# COEXPIX_schematics.net
KiCad netlist of a schematic drawn in Altium Designer
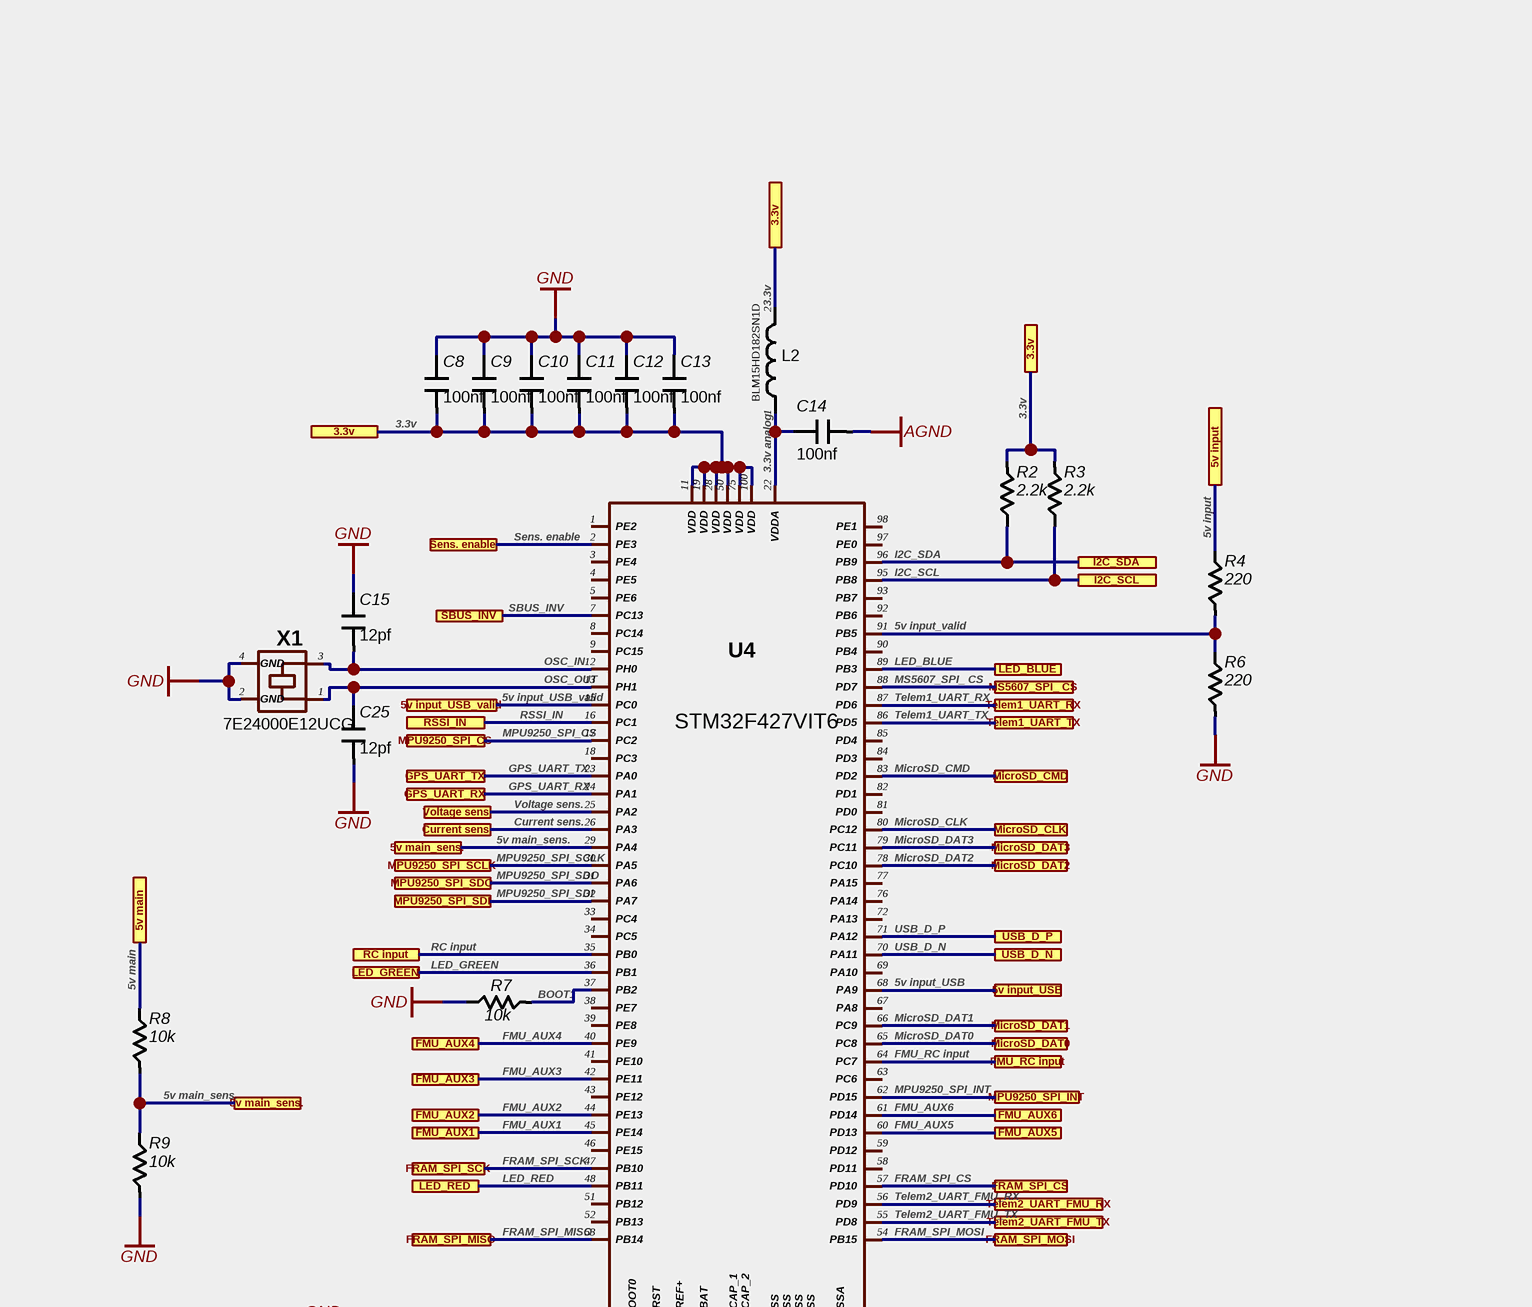
[diagram p0: COEXPIX schematics.SchDoc, top left]
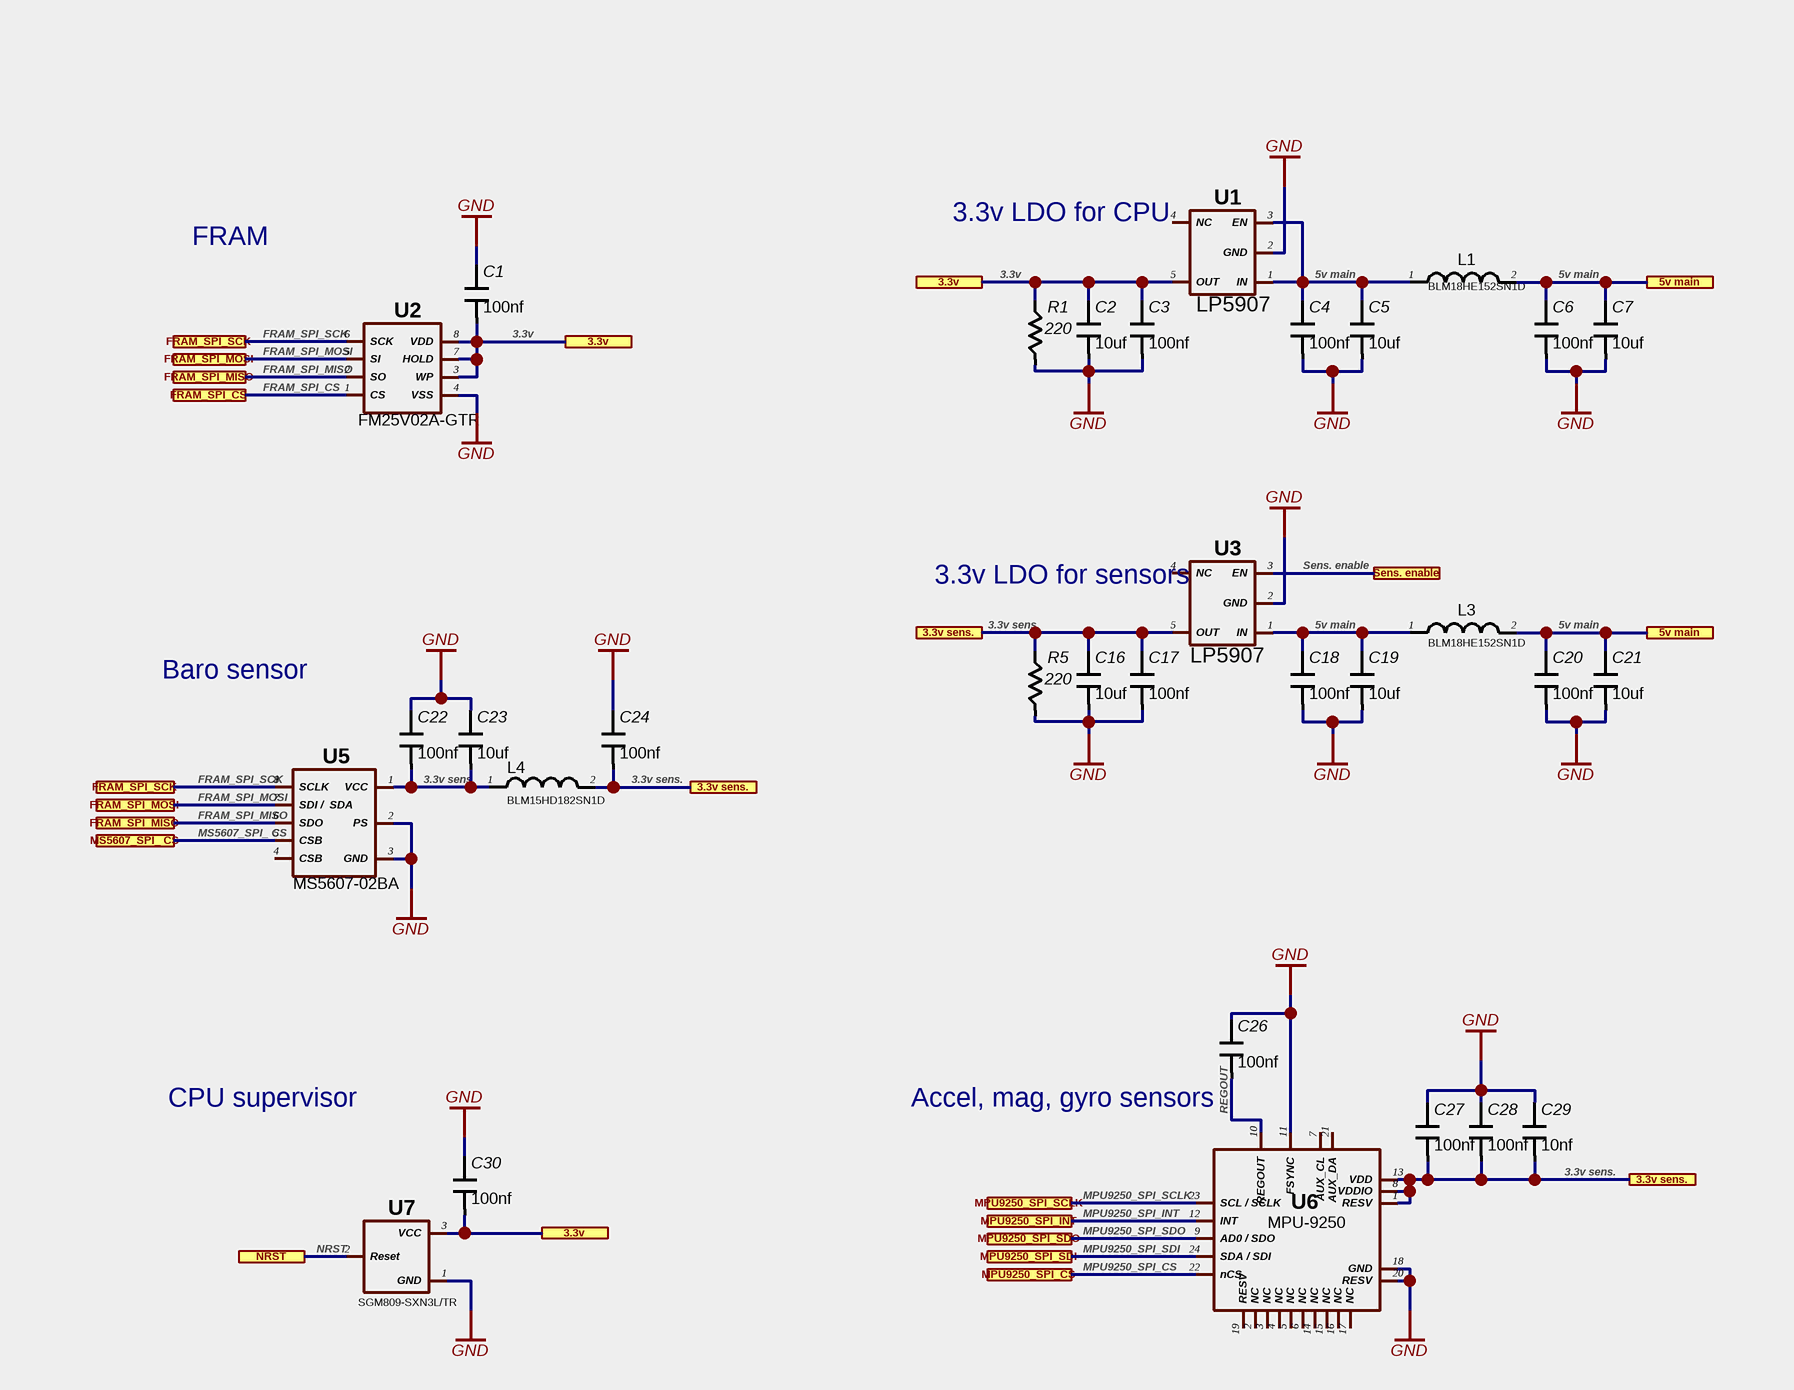
[diagram p1: COEXPIX schematics.SchDoc, top right]
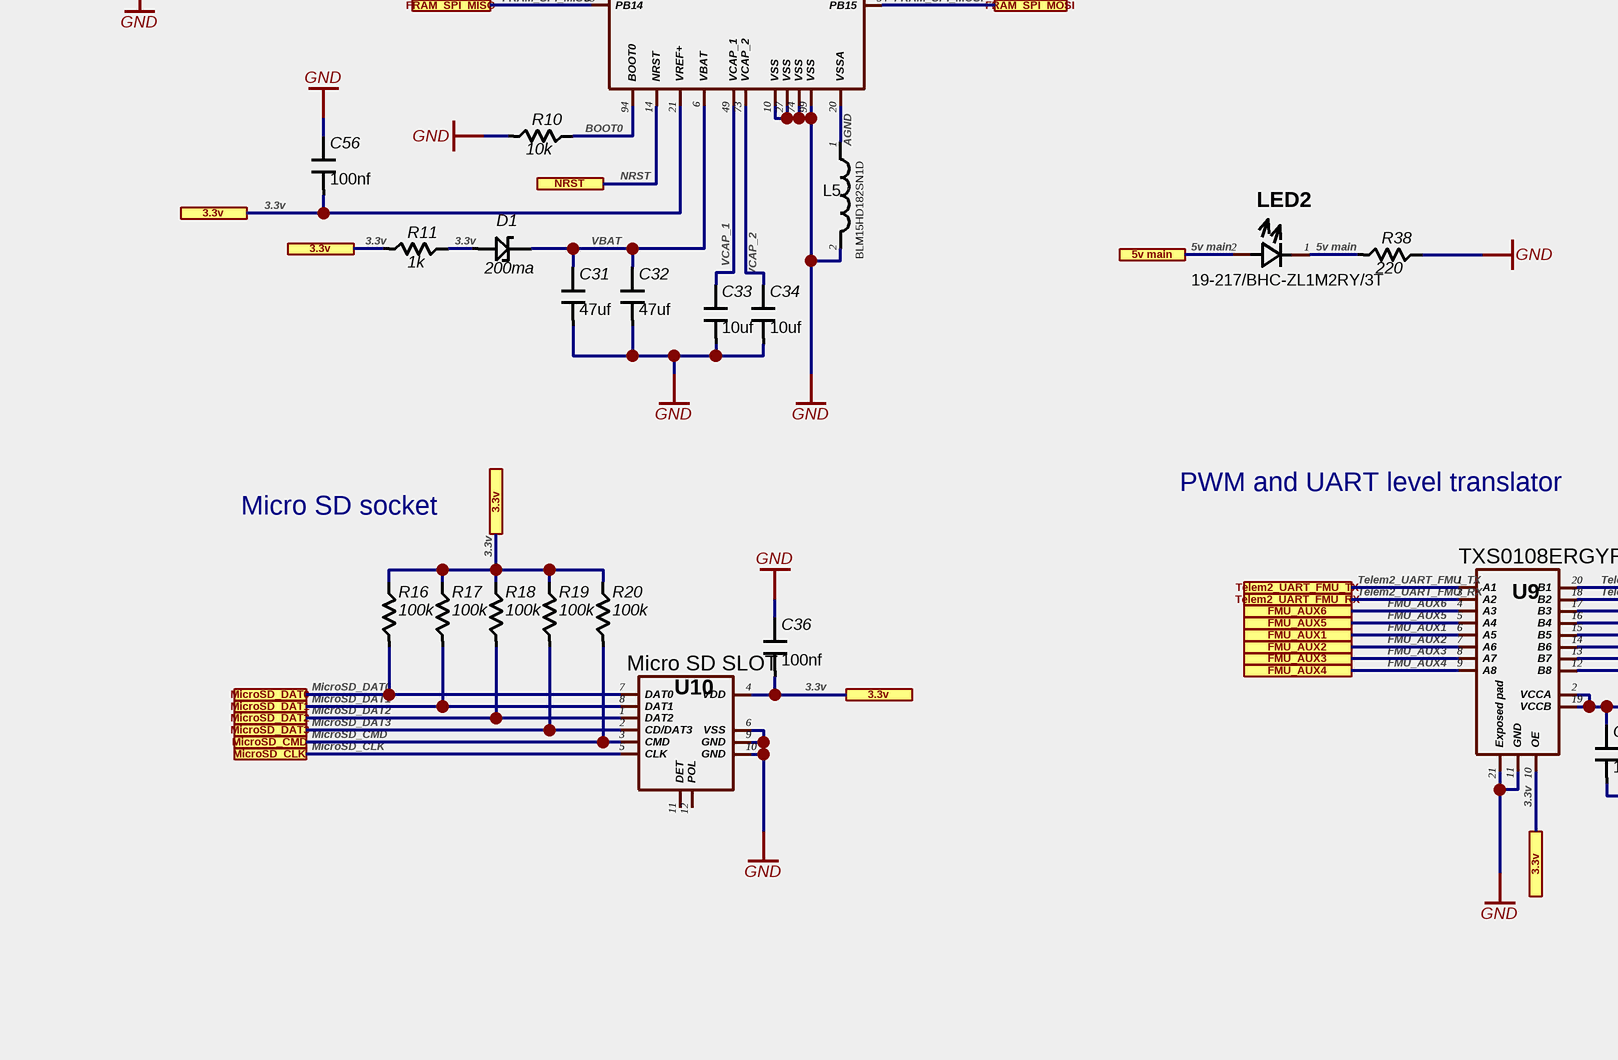
[diagram p2: COEXPIX schematics.SchDoc, bottom left]
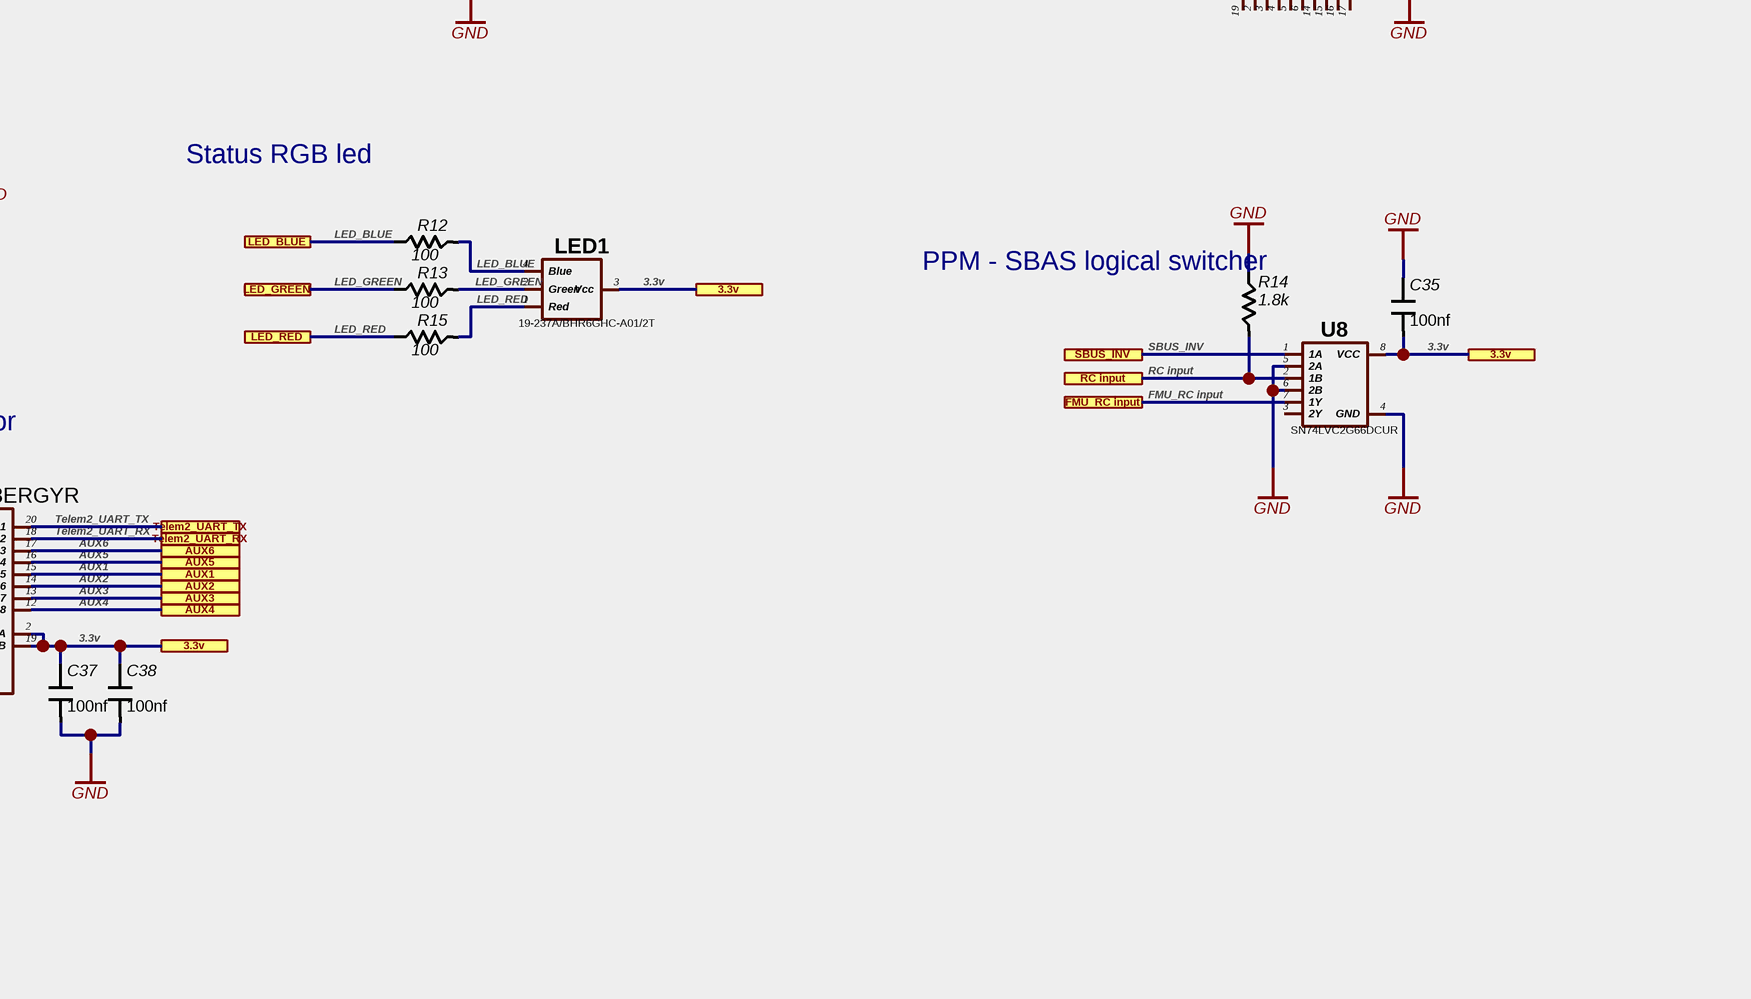
[diagram p3: COEXPIX schematics.SchDoc, bottom right]

(export (version "E")
  (design (tool "Eeschema 10.0.6"))
  (components
    (comp (ref "C1")
      (value "100nf")
      (footprint "Capasitor 0402")
      (description "Multilayer Ceramic Capacitors MLCC - SMD/SMT 100nF 16V 0402")
      (fields (field (name "PART NUMBER") "CC0402KRX7R7BB104") (field (name "MANUFACTURER") "YAGEO"))
      (libsource (lib "Schematic symbols library") (part "Capacitor MLCC"))
    )
    (comp (ref "C2")
      (value "10uf")
      (footprint "Capasitor 0402")
      (description "Multilayer Ceramic Capacitors MLCC - SMD/SMT 10uF 6.3V 0402")
      (fields (field (name "PART NUMBER") "JMK105CBJ106MV-F") (field (name "MANUFACTURER") "Taiyo Yuden"))
      (libsource (lib "Schematic symbols library") (part "Capacitor MLCC"))
    )
    (comp (ref "C3")
      (value "100nf")
      (footprint "Capasitor 0402")
      (description "Multilayer Ceramic Capacitors MLCC - SMD/SMT 100nF 16V 0402")
      (fields (field (name "PART NUMBER") "CC0402KRX7R7BB104") (field (name "MANUFACTURER") "YAGEO"))
      (libsource (lib "Schematic symbols library") (part "Capacitor MLCC"))
    )
    (comp (ref "C4")
      (value "100nf")
      (footprint "Capasitor 0402")
      (description "Multilayer Ceramic Capacitors MLCC - SMD/SMT 100nF 16V 0402")
      (fields (field (name "PART NUMBER") "CC0402KRX7R7BB104") (field (name "MANUFACTURER") "YAGEO"))
      (libsource (lib "Schematic symbols library") (part "Capacitor MLCC"))
    )
    (comp (ref "C5")
      (value "10uf")
      (footprint "Capasitor 0402")
      (description "Multilayer Ceramic Capacitors MLCC - SMD/SMT 10uF 6.3V 0402")
      (fields (field (name "PART NUMBER") "JMK105CBJ106MV-F") (field (name "MANUFACTURER") "Taiyo Yuden"))
      (libsource (lib "") (part "Capacitor MLCC_1"))
    )
    (comp (ref "C6")
      (value "100nf")
      (footprint "Capasitor 0402")
      (description "Multilayer Ceramic Capacitors MLCC - SMD/SMT 100nF 16V 0402")
      (fields (field (name "PART NUMBER") "CC0402KRX7R7BB104") (field (name "MANUFACTURER") "YAGEO"))
      (libsource (lib "Schematic symbols library") (part "Capacitor MLCC"))
    )
    (comp (ref "C7")
      (value "10uf")
      (footprint "Capasitor 0402")
      (description "X5R 6.3v 10uf")
      (fields (field (name "PART NUMBER") "JMK105CBJ106MV-F") (field (name "MANUFACTURER") "Taiyo Yuden"))
      (libsource (lib "Schematic symbols library") (part "Capacitor MLCC"))
    )
    (comp (ref "C8")
      (value "100nf")
      (footprint "Capasitor 0402")
      (description "Multilayer Ceramic Capacitors MLCC - SMD/SMT 100nF 16V 0402")
      (fields (field (name "PART NUMBER") "CC0402KRX7R7BB104") (field (name "MANUFACTURER") "YAGEO"))
      (libsource (lib "Schematic symbols library") (part "Capacitor MLCC"))
    )
    (comp (ref "C9")
      (value "100nf")
      (footprint "Capasitor 0402")
      (description "Multilayer Ceramic Capacitors MLCC - SMD/SMT 100nF 16V 0402")
      (fields (field (name "PART NUMBER") "CC0402KRX7R7BB104") (field (name "MANUFACTURER") "YAGEO"))
      (libsource (lib "Schematic symbols library") (part "Capacitor MLCC"))
    )
    (comp (ref "C10")
      (value "100nf")
      (footprint "Capasitor 0402")
      (description "Multilayer Ceramic Capacitors MLCC - SMD/SMT 100nF 16V 0402")
      (fields (field (name "PART NUMBER") "CC0402KRX7R7BB104") (field (name "MANUFACTURER") "YAGEO"))
      (libsource (lib "Schematic symbols library") (part "Capacitor MLCC"))
    )
    (comp (ref "C11")
      (value "100nf")
      (footprint "Capasitor 0402")
      (description "Multilayer Ceramic Capacitors MLCC - SMD/SMT 100nF 16V 0402")
      (fields (field (name "PART NUMBER") "CC0402KRX7R7BB104") (field (name "MANUFACTURER") "YAGEO"))
      (libsource (lib "Schematic symbols library") (part "Capacitor MLCC"))
    )
    (comp (ref "C12")
      (value "100nf")
      (footprint "Capasitor 0402")
      (description "Multilayer Ceramic Capacitors MLCC - SMD/SMT 100nF 16V 0402")
      (fields (field (name "PART NUMBER") "CC0402KRX7R7BB104") (field (name "MANUFACTURER") "YAGEO"))
      (libsource (lib "Schematic symbols library") (part "Capacitor MLCC"))
    )
    (comp (ref "C13")
      (value "100nf")
      (footprint "Capasitor 0402")
      (description "Multilayer Ceramic Capacitors MLCC - SMD/SMT 100nF 16V 0402")
      (fields (field (name "PART NUMBER") "CC0402KRX7R7BB104") (field (name "MANUFACTURER") "YAGEO"))
      (libsource (lib "Schematic symbols library") (part "Capacitor MLCC"))
    )
    (comp (ref "C14")
      (value "100nf")
      (footprint "Capasitor 0402")
      (description "Multilayer Ceramic Capacitors MLCC - SMD/SMT 100nF 16V 0402")
      (fields (field (name "PART NUMBER") "CC0402KRX7R7BB104") (field (name "MANUFACTURER") "YAGEO"))
      (libsource (lib "Schematic symbols library") (part "Capacitor MLCC"))
    )
    (comp (ref "C15")
      (value "12pf")
      (footprint "Capasitor 0402")
      (description "Multilayer Ceramic Capacitors MLCC - SMD/SMT 12pF 50V 0402")
      (fields (field (name "PART NUMBER") "CC0402JRNPO9BN120") (field (name "MANUFACTURER") "YAGEO"))
      (libsource (lib "Schematic symbols library") (part "Capacitor MLCC"))
    )
    (comp (ref "C16")
      (value "10uf")
      (footprint "Capasitor 0402")
      (description "Multilayer Ceramic Capacitors MLCC - SMD/SMT 10uF 6.3V 0402")
      (fields (field (name "PART NUMBER") "JMK105CBJ106MV-F") (field (name "MANUFACTURER") "Taiyo Yuden"))
      (libsource (lib "Schematic symbols library") (part "Capacitor MLCC"))
    )
    (comp (ref "C17")
      (value "100nf")
      (footprint "Capasitor 0402")
      (description "Multilayer Ceramic Capacitors MLCC - SMD/SMT 100nF 16V 0402")
      (fields (field (name "PART NUMBER") "CC0402KRX7R7BB104") (field (name "MANUFACTURER") "YAGEO"))
      (libsource (lib "Schematic symbols library") (part "Capacitor MLCC"))
    )
    (comp (ref "C18")
      (value "100nf")
      (footprint "Capasitor 0402")
      (description "Multilayer Ceramic Capacitors MLCC - SMD/SMT 100nF 16V 0402")
      (fields (field (name "PART NUMBER") "CC0402KRX7R7BB104") (field (name "MANUFACTURER") "YAGEO"))
      (libsource (lib "Schematic symbols library") (part "Capacitor MLCC"))
    )
    (comp (ref "C19")
      (value "10uf")
      (footprint "Capasitor 0402")
      (description "Multilayer Ceramic Capacitors MLCC - SMD/SMT 10uF 6.3V 0402")
      (fields (field (name "PART NUMBER") "JMK105CBJ106MV-F") (field (name "MANUFACTURER") "Taiyo Yuden"))
      (libsource (lib "") (part "Capacitor MLCC_1"))
    )
    (comp (ref "C20")
      (value "100nf")
      (footprint "Capasitor 0402")
      (description "Multilayer Ceramic Capacitors MLCC - SMD/SMT 100nF 16V 0402")
      (fields (field (name "PART NUMBER") "CC0402KRX7R7BB104") (field (name "MANUFACTURER") "YAGEO"))
      (libsource (lib "Schematic symbols library") (part "Capacitor MLCC"))
    )
    (comp (ref "C21")
      (value "10uf")
      (footprint "Capasitor 0402")
      (description "X5R 6.3v 10uf")
      (fields (field (name "PART NUMBER") "JMK105CBJ106MV-F") (field (name "MANUFACTURER") "Taiyo Yuden"))
      (libsource (lib "Schematic symbols library") (part "Capacitor MLCC"))
    )
    (comp (ref "C22")
      (value "100nf")
      (footprint "Capasitor 0402")
      (description "Multilayer Ceramic Capacitors MLCC - SMD/SMT 100nF 16V 0402")
      (fields (field (name "PART NUMBER") "CC0402KRX7R7BB104") (field (name "MANUFACTURER") "YAGEO"))
      (libsource (lib "Schematic symbols library") (part "Capacitor MLCC"))
    )
    (comp (ref "C23")
      (value "10uf")
      (footprint "Capasitor 0402")
      (description "X5R 6.3v 10uf")
      (fields (field (name "PART NUMBER") "JMK105CBJ106MV-F") (field (name "MANUFACTURER") "Taiyo Yuden"))
      (libsource (lib "Schematic symbols library") (part "Capacitor MLCC"))
    )
    (comp (ref "C24")
      (value "100nf")
      (footprint "Capasitor 0402")
      (description "Multilayer Ceramic Capacitors MLCC - SMD/SMT 100nF 16V 0402")
      (fields (field (name "PART NUMBER") "CC0402KRX7R7BB104") (field (name "MANUFACTURER") "YAGEO"))
      (libsource (lib "Schematic symbols library") (part "Capacitor MLCC"))
    )
    (comp (ref "C25")
      (value "12pf")
      (footprint "Capasitor 0402")
      (description "Multilayer Ceramic Capacitors MLCC - SMD/SMT 12pF 50V 0402")
      (fields (field (name "PART NUMBER") "CC0402JRNPO9BN120") (field (name "MANUFACTURER") "YAGEO"))
      (libsource (lib "Schematic symbols library") (part "Capacitor MLCC"))
    )
    (comp (ref "C26")
      (value "100nf")
      (footprint "Capasitor 0402")
      (description "Multilayer Ceramic Capacitors MLCC - SMD/SMT 100nF 16V 0402")
      (fields (field (name "PART NUMBER") "CC0402KRX7R7BB104") (field (name "MANUFACTURER") "YAGEO"))
      (libsource (lib "Schematic symbols library") (part "Capacitor MLCC"))
    )
    (comp (ref "C27")
      (value "100nf")
      (footprint "Capasitor 0402")
      (description "Multilayer Ceramic Capacitors MLCC - SMD/SMT 100nF 16V 0402")
      (fields (field (name "PART NUMBER") "CC0402KRX7R7BB104") (field (name "MANUFACTURER") "YAGEO"))
      (libsource (lib "Schematic symbols library") (part "Capacitor MLCC"))
    )
    (comp (ref "C28")
      (value "100nf")
      (footprint "Capasitor 0402")
      (description "Multilayer Ceramic Capacitors MLCC - SMD/SMT 100nF 16V 0402")
      (fields (field (name "PART NUMBER") "CC0402KRX7R7BB104") (field (name "MANUFACTURER") "YAGEO"))
      (libsource (lib "Schematic symbols library") (part "Capacitor MLCC"))
    )
    (comp (ref "C29")
      (value "10nf")
      (footprint "Capasitor 0402")
      (description "Multilayer Ceramic Capacitors MLCC - SMD/SMT 10nF 50V 0402")
      (fields (field (name "PART NUMBER") "CC0402KRX7R9BB103") (field (name "MANUFACTURER") "YAGEO"))
      (libsource (lib "Schematic symbols library") (part "Capacitor MLCC"))
    )
    (comp (ref "C30")
      (value "100nf")
      (footprint "Capasitor 0402")
      (description "Multilayer Ceramic Capacitors MLCC - SMD/SMT 100nF 16V 0402")
      (fields (field (name "PART NUMBER") "CC0402KRX7R7BB104") (field (name "MANUFACTURER") "YAGEO"))
      (libsource (lib "Schematic symbols library") (part "Capacitor MLCC"))
    )
    (comp (ref "C31")
      (value "47uf")
      (footprint "Capasitor 0603")
      (description "Multilayer Ceramic Capacitors MLCC - SMD/SMT 47uF 6.3V 0603")
      (fields (field (name "PART NUMBER") "GRM188R60J476ME15D") (field (name "MANUFACTURER") "Murata"))
      (libsource (lib "Schematic symbols library") (part "Capacitor MLCC"))
    )
    (comp (ref "C32")
      (value "47uf")
      (footprint "Capasitor 0603")
      (description "Multilayer Ceramic Capacitors MLCC - SMD/SMT 47uF 6.3V 0603")
      (fields (field (name "PART NUMBER") "GRM188R60J476ME15D") (field (name "MANUFACTURER") "Murata"))
      (libsource (lib "Schematic symbols library") (part "Capacitor MLCC"))
    )
    (comp (ref "C33")
      (value "10uf")
      (footprint "Capasitor 0402")
      (description "Multilayer Ceramic Capacitors MLCC - SMD/SMT 10uF 6.3V 0402")
      (fields (field (name "PART NUMBER") "JMK105CBJ106MV-F") (field (name "MANUFACTURER") "Taiyo Yuden"))
      (libsource (lib "Schematic symbols library") (part "Capacitor MLCC"))
    )
    (comp (ref "C34")
      (value "10uf")
      (footprint "Capasitor 0402")
      (description "Multilayer Ceramic Capacitors MLCC - SMD/SMT 10uF 6.3V 0402")
      (fields (field (name "PART NUMBER") "JMK105CBJ106MV-F") (field (name "MANUFACTURER") "Taiyo Yuden"))
      (libsource (lib "Schematic symbols library") (part "Capacitor MLCC"))
    )
    (comp (ref "C35")
      (value "100nf")
      (footprint "Capasitor 0402")
      (description "Multilayer Ceramic Capacitors MLCC - SMD/SMT 100nF 16V 0402")
      (fields (field (name "PART NUMBER") "CC0402KRX7R7BB104") (field (name "MANUFACTURER") "YAGEO"))
      (libsource (lib "Schematic symbols library") (part "Capacitor MLCC"))
    )
    (comp (ref "C36")
      (value "100nf")
      (footprint "Capasitor 0402")
      (description "Multilayer Ceramic Capacitors MLCC - SMD/SMT 100nF 16V 0402")
      (fields (field (name "PART NUMBER") "CC0402KRX7R7BB104") (field (name "MANUFACTURER") "YAGEO"))
      (libsource (lib "Schematic symbols library") (part "Capacitor MLCC"))
    )
    (comp (ref "C37")
      (value "100nf")
      (footprint "Capasitor 0402")
      (description "Multilayer Ceramic Capacitors MLCC - SMD/SMT 100nF 16V 0402")
      (fields (field (name "PART NUMBER") "CC0402KRX7R7BB104") (field (name "MANUFACTURER") "YAGEO"))
      (libsource (lib "Schematic symbols library") (part "Capacitor MLCC"))
    )
    (comp (ref "C38")
      (value "100nf")
      (footprint "Capasitor 0402")
      (description "Multilayer Ceramic Capacitors MLCC - SMD/SMT 100nF 16V 0402")
      (fields (field (name "PART NUMBER") "CC0402KRX7R7BB104") (field (name "MANUFACTURER") "YAGEO"))
      (libsource (lib "Schematic symbols library") (part "Capacitor MLCC"))
    )
    (comp (ref "C56")
      (value "100nf")
      (footprint "Capasitor 0402")
      (description "Multilayer Ceramic Capacitors MLCC - SMD/SMT 100nF 16V 0402")
      (fields (field (name "PART NUMBER") "CC0402KRX7R7BB104") (field (name "MANUFACTURER") "YAGEO"))
      (libsource (lib "Schematic symbols library") (part "Capacitor MLCC"))
    )
    (comp (ref "D1")
      (value "200ma")
      (footprint "SOD-523F")
      (description "Schottky Barrier Diodes (SBD) SOD-523")
      (fields (field (name "PART NUMBER") "RB521S-30") (field (name "MANUFACTURER") "Shikues"))
      (libsource (lib "Schematic symbols library") (part "Schottky barrier diode"))
    )
    (comp (ref "L1")
      (value "BLM18HE152SN1D")
      (footprint "Ferrite bead 0603")
      (description "Beads 0603")
      (fields (field (name "MANUFACTURER") "Murata"))
      (libsource (lib "Schematic symbols library") (part "FB / Inductor"))
    )
    (comp (ref "L2")
      (value "BLM15HD182SN1D")
      (footprint "Ferrite bead 0402")
      (description "Beads 0402")
      (fields (field (name "MANUFACTURER") "Murata Electronics"))
      (libsource (lib "Schematic symbols library") (part "FB / Inductor"))
    )
    (comp (ref "L3")
      (value "BLM18HE152SN1D")
      (footprint "Ferrite bead 0603")
      (description "Beads 0603")
      (fields (field (name "MANUFACTURER") "Murata"))
      (libsource (lib "Schematic symbols library") (part "FB / Inductor"))
    )
    (comp (ref "L4")
      (value "BLM15HD182SN1D")
      (footprint "Ferrite bead 0402")
      (description "Beads 0402")
      (fields (field (name "MANUFACTURER") "Murata Electronics"))
      (libsource (lib "Schematic symbols library") (part "FB / Inductor"))
    )
    (comp (ref "L5")
      (value "BLM15HD182SN1D")
      (footprint "Ferrite bead 0402")
      (description "Beads 0402")
      (fields (field (name "MANUFACTURER") "Murata Electronics"))
      (libsource (lib "Schematic symbols library") (part "FB / Inductor"))
    )
    (comp (ref "LED1")
      (value "19-237A/BHR6GHC-A01/2T")
      (footprint "Everlight RGB LED")
      (description "RGB LED")
      (fields (field (name "MANUFACTURER") "Everlight"))
      (libsource (lib "Schematic symbols library") (part "Everlight 19-237A"))
    )
    (comp (ref "LED2")
      (value "19-217/BHC-ZL1M2RY/3T")
      (footprint "Led 0603")
      (description "Light Emitting Diodes (LED) Blue 465~475nm 11.5~28.5mcd@5mA Top View 0603")
      (fields (field (name "MANUFACTURER") "Everlight Elec"))
      (libsource (lib "Schematic symbols library") (part "LED"))
    )
    (comp (ref "R1")
      (value "220")
      (footprint "Resistor 0603")
      (description "Chip Resistor - Surface Mount 220Ohms ±1% 1/10W 0603")
      (fields (field (name "PART NUMBER") "0603WAF2200T5E") (field (name "MANUFACTURER") "Uniroyal Elec"))
      (libsource (lib "Schematic symbols library") (part "Resistor"))
    )
    (comp (ref "R2")
      (value "2.2k")
      (footprint "Resistor 0402")
      (description "Chip Resistor - Surface Mount 2.2KOhms ±1% 1/16W 0402")
      (fields (field (name "PART NUMBER") "RC0402FR-072K2L") (field (name "MANUFACTURER") "YAGEO"))
      (libsource (lib "Schematic symbols library") (part "Resistor"))
    )
    (comp (ref "R3")
      (value "2.2k")
      (footprint "Resistor 0402")
      (description "Chip Resistor - Surface Mount 2.2KOhms ±1% 1/16W 0402")
      (fields (field (name "PART NUMBER") "RC0402FR-072K2L") (field (name "MANUFACTURER") "YAGEO"))
      (libsource (lib "Schematic symbols library") (part "Resistor"))
    )
    (comp (ref "R4")
      (value "220")
      (footprint "Resistor 0402")
      (description "Chip Resistor - Surface Mount 220Ohms ±1% 1/16W 0402")
      (fields (field (name "PART NUMBER") "0402WGF2200TCE") (field (name "MANUFACTURER") "Uniroyal Elec"))
      (libsource (lib "Schematic symbols library") (part "Resistor"))
    )
    (comp (ref "R5")
      (value "220")
      (footprint "Resistor 0603")
      (description "Chip Resistor - Surface Mount 220Ohms ±1% 1/10W 0603")
      (fields (field (name "PART NUMBER") "0603WAF2200T5E") (field (name "MANUFACTURER") "Uniroyal Elec"))
      (libsource (lib "Schematic symbols library") (part "Resistor"))
    )
    (comp (ref "R6")
      (value "220")
      (footprint "Resistor 0402")
      (description "Chip Resistor - Surface Mount 220Ohms ±1% 1/16W 0402")
      (fields (field (name "PART NUMBER") "0402WGF2200TCE") (field (name "MANUFACTURER") "Uniroyal Elec"))
      (libsource (lib "Schematic symbols library") (part "Resistor"))
    )
    (comp (ref "R7")
      (value "10k")
      (footprint "Resistor 0402")
      (description "Chip Resistor - Surface Mount 10KOhms ±1% 1/16W 0402")
      (fields (field (name "PART NUMBER") "RC0402FR-0710KL") (field (name "MANUFACTURER") "YAGEO"))
      (libsource (lib "Schematic symbols library") (part "Resistor"))
    )
    (comp (ref "R8")
      (value "10k")
      (footprint "Resistor 0402")
      (description "Chip Resistor - Surface Mount 10KOhms ±1% 1/16W 0402")
      (fields (field (name "PART NUMBER") "RC0402FR-0710KL") (field (name "MANUFACTURER") "YAGEO"))
      (libsource (lib "Schematic symbols library") (part "Resistor"))
    )
    (comp (ref "R9")
      (value "10k")
      (footprint "Resistor 0402")
      (description "Chip Resistor - Surface Mount 10KOhms ±1% 1/16W 0402")
      (fields (field (name "PART NUMBER") "RC0402FR-0710KL") (field (name "MANUFACTURER") "YAGEO"))
      (libsource (lib "Schematic symbols library") (part "Resistor"))
    )
    (comp (ref "R10")
      (value "10k")
      (footprint "Resistor 0402")
      (description "Chip Resistor - Surface Mount 10KOhms ±1% 1/16W 0402")
      (fields (field (name "PART NUMBER") "RC0402FR-0710KL") (field (name "MANUFACTURER") "YAGEO"))
      (libsource (lib "Schematic symbols library") (part "Resistor"))
    )
    (comp (ref "R11")
      (value "1k")
      (footprint "Resistor 0402")
      (description "Chip Resistor - Surface Mount 1KOhms ±1% 1/16W 0402")
      (fields (field (name "PART NUMBER") "RC0402FR-071KL") (field (name "MANUFACTURER") "YAGEO"))
      (libsource (lib "Schematic symbols library") (part "Resistor"))
    )
    (comp (ref "R12")
      (value "100")
      (footprint "Resistor 0402")
      (description "Chip Resistor - Surface Mount 100Ohms ±1% 1/16W 0402")
      (fields (field (name "PART NUMBER") "RC0402FR-07100RL") (field (name "MANUFACTURER") "YAGEO"))
      (libsource (lib "Schematic symbols library") (part "Resistor"))
    )
    (comp (ref "R13")
      (value "100")
      (footprint "Resistor 0402")
      (description "Chip Resistor - Surface Mount 100Ohms ±1% 1/16W 0402")
      (fields (field (name "PART NUMBER") "RC0402FR-07100RL") (field (name "MANUFACTURER") "YAGEO"))
      (libsource (lib "Schematic symbols library") (part "Resistor"))
    )
    (comp (ref "R14")
      (value "1.8k")
      (footprint "Resistor 0402")
      (description "Chip Resistor - Surface Mount 1.8KOhms ±1% 1/16W 0402")
      (fields (field (name "PART NUMBER") "0402WGF1801TCE") (field (name "MANUFACTURER") "Uniroyal Elec"))
      (libsource (lib "Schematic symbols library") (part "Resistor"))
    )
    (comp (ref "R15")
      (value "100")
      (footprint "Resistor 0402")
      (description "Chip Resistor - Surface Mount 100Ohms ±1% 1/16W 0402")
      (fields (field (name "PART NUMBER") "RC0402FR-07100RL") (field (name "MANUFACTURER") "YAGEO"))
      (libsource (lib "Schematic symbols library") (part "Resistor"))
    )
    (comp (ref "R16")
      (value "100k")
      (footprint "Resistor 0402")
      (description "Chip Resistor - Surface Mount 100KOhms ±1% 1/16W 0402")
      (fields (field (name "PART NUMBER") "RC0402FR-07100KL") (field (name "MANUFACTURER") "YAGEO"))
      (libsource (lib "Schematic symbols library") (part "Resistor"))
    )
    (comp (ref "R17")
      (value "100k")
      (footprint "Resistor 0402")
      (description "Chip Resistor - Surface Mount 100KOhms ±1% 1/16W 0402")
      (fields (field (name "PART NUMBER") "RC0402FR-07100KL") (field (name "MANUFACTURER") "YAGEO"))
      (libsource (lib "Schematic symbols library") (part "Resistor"))
    )
    (comp (ref "R18")
      (value "100k")
      (footprint "Resistor 0402")
      (description "Chip Resistor - Surface Mount 100KOhms ±1% 1/16W 0402")
      (fields (field (name "PART NUMBER") "RC0402FR-07100KL") (field (name "MANUFACTURER") "YAGEO"))
      (libsource (lib "Schematic symbols library") (part "Resistor"))
    )
    (comp (ref "R19")
      (value "100k")
      (footprint "Resistor 0402")
      (description "Chip Resistor - Surface Mount 100KOhms ±1% 1/16W 0402")
      (fields (field (name "PART NUMBER") "RC0402FR-07100KL") (field (name "MANUFACTURER") "YAGEO"))
      (libsource (lib "Schematic symbols library") (part "Resistor"))
    )
    (comp (ref "R20")
      (value "100k")
      (footprint "Resistor 0402")
      (description "Chip Resistor - Surface Mount 100KOhms ±1% 1/16W 0402")
      (fields (field (name "PART NUMBER") "RC0402FR-07100KL") (field (name "MANUFACTURER") "YAGEO"))
      (libsource (lib "Schematic symbols library") (part "Resistor"))
    )
    (comp (ref "R38")
      (value "220")
      (footprint "Resistor 0402")
      (description "Chip Resistor - Surface Mount 220Ohms ±1% 1/16W 0402")
      (fields (field (name "PART NUMBER") "0402WGF2200TCE") (field (name "MANUFACTURER") "Uniroyal Elec"))
      (libsource (lib "Schematic symbols library") (part "Resistor"))
    )
    (comp (ref "U1")
      (value "LP5907")
      (footprint "SOT23-5")
      (description "Linear Voltage Regulators SOT-23-5")
      (fields (field (name "MANUFACTURER") "Texas Instruments"))
      (libsource (lib "Schematic symbols library") (part "LP5907"))
    )
    (comp (ref "U2")
      (value "FM25V02A-GTR")
      (footprint "SOIC-8")
      (description "FRAM FRAM 256Kb (32K x 8) SPI SOIC-8_150mil")
      (fields (field (name "MANUFACTURER") "Cypress Semicon"))
      (libsource (lib "Schematic symbols library") (part "FM25V02A"))
    )
    (comp (ref "U3")
      (value "LP5907")
      (footprint "SOT23-5")
      (description "Linear Voltage Regulators SOT-23-5")
      (fields (field (name "MANUFACTURER") "Texas Instruments"))
      (libsource (lib "Schematic symbols library") (part "LP5907"))
    )
    (comp (ref "U4")
      (value "STM32F427VIT6")
      (footprint "LQFP100")
      (description "ARM® Cortex®-M4 STM32F4 Microcontroller IC 32-Bit 180MHz 2MB (2M x 8) FLASH 100-LQFP (14x14)")
      (fields (field (name "MANUFACTURER") "STMicroelectronics"))
      (libsource (lib "Schematic symbols library") (part "STM32F427VIT6"))
    )
    (comp (ref "U5")
      (value "MS5607-02BA")
      (footprint "MS5611")
      (fields (field (name "MANUFACTURER") "meas-spec"))
      (libsource (lib "Schematic symbols library") (part "MS5607-02BA"))
    )
    (comp (ref "U6")
      (value "MPU-9250")
      (footprint "mpu9250")
      (description "IMU ACCEL/GYRO/MAG I2C/SPI 24QFN")
      (fields (field (name "MANUFACTURER") "TDK InvenSense"))
      (libsource (lib "Schematic symbols library") (part "mpu9250"))
    )
    (comp (ref "U7")
      (value "SGM809-SXN3L/TR")
      (footprint "SOT23-3 LP")
      (fields (field (name "MANUFACTURER") "SGMICRO"))
      (libsource (lib "Schematic symbols library") (part "SGM809-SXN3L/TR"))
    )
    (comp (ref "U8")
      (value "SN74LVC2G66DCUR")
      (footprint "VSSOP8 0.5mm")
      (description "74 Series SPST-NC 2 1.65V ~ 5.5V VSSOP-8_2x2.3x05P")
      (fields (field (name "MANUFACTURER") "Texas Instruments"))
      (libsource (lib "Schematic symbols library") (part "SN74LVC2G86DCUR"))
    )
    (comp (ref "U9")
      (value "TXS0108ERGYR")
      (footprint "TXS0108ERGYR")
      (description "Level Translators, Shifters VQFN-20")
      (fields (field (name "MANUFACTURER") "Texas Instruments"))
      (libsource (lib "Schematic symbols library") (part "TXS0108ERGYR"))
    )
    (comp (ref "U10")
      (value "Micro SD SLOT")
      (footprint "Micro SD slot")
      (libsource (lib "Schematic symbols library") (part "MicroSD socket"))
    )
    (comp (ref "X1")
      (value "7E24000E12UCG")
      (footprint "SMD-2520_4P")
      (description "SMD Crystal Resonators 24MHz ±10ppm SMD-2520_4P")
      (fields (field (name "MANUFACTURER") "SHENZHEN CRYSTAL TECH"))
      (libsource (lib "Schematic symbols library") (part "Crystal oscillator"))
    )
  )
  (nets
    (net (code "1") (name "/3.3v") (class "Default")
      (node (ref "C1") (pin "2") (pinfunction "2_2") (pintype "passive"))
      (node (ref "C10") (pin "2") (pinfunction "2_2") (pintype "passive"))
      (node (ref "C11") (pin "2") (pinfunction "2_2") (pintype "passive"))
      (node (ref "C12") (pin "2") (pinfunction "2_2") (pintype "passive"))
      (node (ref "C13") (pin "2") (pinfunction "2_2") (pintype "passive"))
      (node (ref "C2") (pin "1") (pinfunction "1_1") (pintype "passive"))
      (node (ref "C3") (pin "1") (pinfunction "1_1") (pintype "passive"))
      (node (ref "C30") (pin "2") (pinfunction "2_2") (pintype "passive"))
      (node (ref "C35") (pin "2") (pinfunction "2_2") (pintype "passive"))
      (node (ref "C36") (pin "2") (pinfunction "2_2") (pintype "passive"))
      (node (ref "C37") (pin "1") (pinfunction "1_1") (pintype "passive"))
      (node (ref "C38") (pin "1") (pinfunction "1_1") (pintype "passive"))
      (node (ref "C56") (pin "2") (pinfunction "2_2") (pintype "passive"))
      (node (ref "C8") (pin "2") (pinfunction "2_2") (pintype "passive"))
      (node (ref "C9") (pin "2") (pinfunction "2_2") (pintype "passive"))
      (node (ref "D1") (pin "2") (pinfunction "2_2") (pintype "passive"))
      (node (ref "L2") (pin "2") (pintype "power_in"))
      (node (ref "LED1") (pin "3") (pinfunction "Vcc_3") (pintype "power_in"))
      (node (ref "R1") (pin "1") (pinfunction "1_1") (pintype "passive"))
      (node (ref "R11") (pin "1") (pinfunction "1_1") (pintype "passive"))
      (node (ref "R11") (pin "2") (pinfunction "2_2") (pintype "passive"))
      (node (ref "R16") (pin "1") (pinfunction "1_1") (pintype "passive"))
      (node (ref "R17") (pin "1") (pinfunction "1_1") (pintype "passive"))
      (node (ref "R18") (pin "1") (pinfunction "1_1") (pintype "passive"))
      (node (ref "R19") (pin "1") (pinfunction "1_1") (pintype "passive"))
      (node (ref "R2") (pin "2") (pinfunction "2_2") (pintype "passive"))
      (node (ref "R20") (pin "1") (pinfunction "1_1") (pintype "passive"))
      (node (ref "R3") (pin "2") (pinfunction "2_2") (pintype "passive"))
      (node (ref "U1") (pin "5") (pinfunction "OUT_5") (pintype "power_in"))
      (node (ref "U10") (pin "4") (pinfunction "VDD_4") (pintype "power_in"))
      (node (ref "U2") (pin "3") (pinfunction "WP_3") (pintype "power_in"))
      (node (ref "U2") (pin "7") (pinfunction "HOLD_7") (pintype "power_in"))
      (node (ref "U2") (pin "8") (pinfunction "VDD_8") (pintype "power_in"))
      (node (ref "U4") (pin "100") (pinfunction "VDD_100") (pintype "power_in"))
      (node (ref "U4") (pin "11") (pinfunction "VDD_11") (pintype "power_in"))
      (node (ref "U4") (pin "19") (pinfunction "VDD_19") (pintype "power_in"))
      (node (ref "U4") (pin "21") (pinfunction "VREF+_21") (pintype "power_in"))
      (node (ref "U4") (pin "28") (pinfunction "VDD_28") (pintype "power_in"))
      (node (ref "U4") (pin "50") (pinfunction "VDD_50") (pintype "power_in"))
      (node (ref "U4") (pin "75") (pinfunction "VDD_75") (pintype "power_in"))
      (node (ref "U7") (pin "3") (pinfunction "VCC_3") (pintype "power_in"))
      (node (ref "U8") (pin "8") (pinfunction "VCC_8") (pintype "power_in"))
      (node (ref "U9") (pin "10") (pinfunction "OE_10") (pintype "power_in"))
      (node (ref "U9") (pin "19") (pinfunction "VCCB_19") (pintype "power_in"))
      (node (ref "U9") (pin "2") (pinfunction "VCCA_2") (pintype "power_in"))
    )
    (net (code "2") (name "/3.3v analog") (class "Default")
      (node (ref "C14") (pin "1") (pinfunction "1_1") (pintype "passive"))
      (node (ref "L2") (pin "1") (pintype "power_in"))
      (node (ref "U4") (pin "22") (pinfunction "VDDA_22") (pintype "power_in"))
    )
    (net (code "3") (name "/3.3v sens.") (class "Default")
      (node (ref "C16") (pin "1") (pinfunction "1_1") (pintype "passive"))
      (node (ref "C17") (pin "1") (pinfunction "1_1") (pintype "passive"))
      (node (ref "C22") (pin "2") (pinfunction "2_2") (pintype "passive"))
      (node (ref "C23") (pin "2") (pinfunction "2_2") (pintype "passive"))
      (node (ref "C24") (pin "2") (pinfunction "2_2") (pintype "passive"))
      (node (ref "C27") (pin "2") (pinfunction "2_2") (pintype "passive"))
      (node (ref "C28") (pin "2") (pinfunction "2_2") (pintype "passive"))
      (node (ref "C29") (pin "2") (pinfunction "2_2") (pintype "passive"))
      (node (ref "L4") (pin "1") (pintype "power_in"))
      (node (ref "L4") (pin "2") (pintype "power_in"))
      (node (ref "R5") (pin "1") (pinfunction "1_1") (pintype "passive"))
      (node (ref "U3") (pin "5") (pinfunction "OUT_5") (pintype "power_in"))
      (node (ref "U5") (pin "1") (pinfunction "VCC_1") (pintype "power_in"))
      (node (ref "U6") (pin "1") (pinfunction "RESV_1") (pintype "power_in"))
      (node (ref "U6") (pin "13") (pinfunction "VDD_13") (pintype "power_in"))
      (node (ref "U6") (pin "8") (pinfunction "VDDIO_8") (pintype "power_in"))
    )
    (net (code "4") (name "/5v input") (class "Default")
      (node (ref "R4") (pin "1") (pinfunction "1_1") (pintype "passive"))
    )
    (net (code "5") (name "/5v input_USB") (class "Default")
      (node (ref "U4") (pin "68") (pinfunction "PA9_68") (pintype "power_in"))
    )
    (net (code "6") (name "/5v input_USB_valid") (class "Default")
      (node (ref "U4") (pin "15") (pinfunction "PC0_15") (pintype "power_in"))
    )
    (net (code "7") (name "/5v input_valid") (class "Default")
      (node (ref "R4") (pin "2") (pinfunction "2_2") (pintype "passive"))
      (node (ref "R6") (pin "1") (pinfunction "1_1") (pintype "passive"))
      (node (ref "U4") (pin "91") (pinfunction "PB5_91") (pintype "power_in"))
    )
    (net (code "8") (name "/5v main") (class "Default")
      (node (ref "C18") (pin "1") (pinfunction "1_1") (pintype "passive"))
      (node (ref "C19") (pin "1") (pinfunction "1_1") (pintype "passive"))
      (node (ref "C20") (pin "1") (pinfunction "1_1") (pintype "passive"))
      (node (ref "C21") (pin "1") (pinfunction "1_1") (pintype "passive"))
      (node (ref "C4") (pin "1") (pinfunction "1_1") (pintype "passive"))
      (node (ref "C5") (pin "1") (pinfunction "1_1") (pintype "passive"))
      (node (ref "C6") (pin "1") (pinfunction "1_1") (pintype "passive"))
      (node (ref "C7") (pin "1") (pinfunction "1_1") (pintype "passive"))
      (node (ref "L1") (pin "1") (pintype "power_in"))
      (node (ref "L1") (pin "2") (pintype "power_in"))
      (node (ref "L3") (pin "1") (pintype "power_in"))
      (node (ref "L3") (pin "2") (pintype "power_in"))
      (node (ref "LED2") (pin "1") (pintype "power_in"))
      (node (ref "LED2") (pin "2") (pintype "power_in"))
      (node (ref "R38") (pin "2") (pinfunction "2_2") (pintype "passive"))
      (node (ref "R8") (pin "1") (pinfunction "1_1") (pintype "passive"))
      (node (ref "U1") (pin "1") (pinfunction "IN_1") (pintype "power_in"))
      (node (ref "U1") (pin "3") (pinfunction "EN_3") (pintype "power_in"))
      (node (ref "U3") (pin "1") (pinfunction "IN_1") (pintype "power_in"))
    )
    (net (code "9") (name "/5v main_sens.") (class "Default")
      (node (ref "R8") (pin "2") (pinfunction "2_2") (pintype "passive"))
      (node (ref "R9") (pin "1") (pinfunction "1_1") (pintype "passive"))
      (node (ref "U4") (pin "29") (pinfunction "PA4_29") (pintype "power_in"))
    )
    (net (code "10") (name "/AUX1") (class "Default")
      (node (ref "U9") (pin "15") (pinfunction "B5_15") (pintype "power_in"))
    )
    (net (code "11") (name "/AUX2") (class "Default")
      (node (ref "U9") (pin "14") (pinfunction "B6_14") (pintype "power_in"))
    )
    (net (code "12") (name "/AUX3") (class "Default")
      (node (ref "U9") (pin "13") (pinfunction "B7_13") (pintype "power_in"))
    )
    (net (code "13") (name "/AUX4") (class "Default")
      (node (ref "U9") (pin "12") (pinfunction "B8_12") (pintype "power_in"))
    )
    (net (code "14") (name "/AUX5") (class "Default")
      (node (ref "U9") (pin "16") (pinfunction "B4_16") (pintype "power_in"))
    )
    (net (code "15") (name "/AUX6") (class "Default")
      (node (ref "U9") (pin "17") (pinfunction "B3_17") (pintype "power_in"))
    )
    (net (code "16") (name "/BOOT0") (class "Default")
      (node (ref "R10") (pin "1") (pinfunction "1_1") (pintype "passive"))
      (node (ref "U4") (pin "94") (pinfunction "BOOT0_94") (pintype "power_in"))
    )
    (net (code "17") (name "/BOOT1") (class "Default")
      (node (ref "R7") (pin "2") (pinfunction "2_2") (pintype "passive"))
      (node (ref "U4") (pin "37") (pinfunction "PB2_37") (pintype "power_in"))
    )
    (net (code "18") (name "/Current sens.") (class "Default")
      (node (ref "U4") (pin "26") (pinfunction "PA3_26") (pintype "power_in"))
    )
    (net (code "19") (name "/FMU_AUX1") (class "Default")
      (node (ref "U4") (pin "45") (pinfunction "PE14_45") (pintype "power_in"))
      (node (ref "U9") (pin "6") (pinfunction "A5_6") (pintype "power_in"))
    )
    (net (code "20") (name "/FMU_AUX2") (class "Default")
      (node (ref "U4") (pin "44") (pinfunction "PE13_44") (pintype "power_in"))
      (node (ref "U9") (pin "7") (pinfunction "A6_7") (pintype "power_in"))
    )
    (net (code "21") (name "/FMU_AUX3") (class "Default")
      (node (ref "U4") (pin "42") (pinfunction "PE11_42") (pintype "power_in"))
      (node (ref "U9") (pin "8") (pinfunction "A7_8") (pintype "power_in"))
    )
    (net (code "22") (name "/FMU_AUX4") (class "Default")
      (node (ref "U4") (pin "40") (pinfunction "PE9_40") (pintype "power_in"))
      (node (ref "U9") (pin "9") (pinfunction "A8_9") (pintype "power_in"))
    )
    (net (code "23") (name "/FMU_AUX5") (class "Default")
      (node (ref "U4") (pin "60") (pinfunction "PD13_60") (pintype "power_in"))
      (node (ref "U9") (pin "5") (pinfunction "A4_5") (pintype "power_in"))
    )
    (net (code "24") (name "/FMU_AUX6") (class "Default")
      (node (ref "U4") (pin "61") (pinfunction "PD14_61") (pintype "power_in"))
      (node (ref "U9") (pin "4") (pinfunction "A3_4") (pintype "power_in"))
    )
    (net (code "25") (name "/FMU_RC input") (class "Default")
      (node (ref "U4") (pin "64") (pinfunction "PC7_64") (pintype "power_in"))
      (node (ref "U8") (pin "7") (pinfunction "1Y_7") (pintype "power_in"))
    )
    (net (code "26") (name "/FRAM_SPI_CS") (class "Default")
      (node (ref "U2") (pin "1") (pinfunction "CS_1") (pintype "power_in"))
      (node (ref "U4") (pin "57") (pinfunction "PD10_57") (pintype "power_in"))
    )
    (net (code "27") (name "/FRAM_SPI_MISO") (class "Default")
      (node (ref "U2") (pin "2") (pinfunction "SO_2") (pintype "power_in"))
      (node (ref "U4") (pin "53") (pinfunction "PB14_53") (pintype "power_in"))
      (node (ref "U5") (pin "6") (pinfunction "SDO_6") (pintype "power_in"))
    )
    (net (code "28") (name "/FRAM_SPI_MOSI") (class "Default")
      (node (ref "U2") (pin "5") (pinfunction "SI_5") (pintype "power_in"))
      (node (ref "U4") (pin "54") (pinfunction "PB15_54") (pintype "power_in"))
      (node (ref "U5") (pin "7") (pinfunction "SDI_/__SDA_7") (pintype "power_in"))
    )
    (net (code "29") (name "/FRAM_SPI_SCK") (class "Default")
      (node (ref "U2") (pin "6") (pinfunction "SCK_6") (pintype "power_in"))
      (node (ref "U4") (pin "47") (pinfunction "PB10_47") (pintype "power_in"))
      (node (ref "U5") (pin "8") (pinfunction "SCLK_8") (pintype "power_in"))
    )
    (net (code "30") (name "/GPS_UART_RX") (class "Default")
      (node (ref "U4") (pin "24") (pinfunction "PA1_24") (pintype "power_in"))
    )
    (net (code "31") (name "/GPS_UART_TX") (class "Default")
      (node (ref "U4") (pin "23") (pinfunction "PA0_23") (pintype "power_in"))
    )
    (net (code "32") (name "/I2C_SCL") (class "Default")
      (node (ref "R3") (pin "1") (pinfunction "1_1") (pintype "passive"))
      (node (ref "U4") (pin "95") (pinfunction "PB8_95") (pintype "power_in"))
    )
    (net (code "33") (name "/I2C_SDA") (class "Default")
      (node (ref "R2") (pin "1") (pinfunction "1_1") (pintype "passive"))
      (node (ref "U4") (pin "96") (pinfunction "PB9_96") (pintype "power_in"))
    )
    (net (code "34") (name "/LED_BLUE") (class "Default")
      (node (ref "LED1") (pin "4") (pinfunction "Blue_4") (pintype "power_in"))
      (node (ref "R12") (pin "1") (pinfunction "1_1") (pintype "passive"))
      (node (ref "R12") (pin "2") (pinfunction "2_2") (pintype "passive"))
      (node (ref "U4") (pin "89") (pinfunction "PB3_89") (pintype "power_in"))
    )
    (net (code "35") (name "/LED_GREEN") (class "Default")
      (node (ref "LED1") (pin "2") (pinfunction "Green_2") (pintype "power_in"))
      (node (ref "R13") (pin "1") (pinfunction "1_1") (pintype "passive"))
      (node (ref "R13") (pin "2") (pinfunction "2_2") (pintype "passive"))
      (node (ref "U4") (pin "36") (pinfunction "PB1_36") (pintype "power_in"))
    )
    (net (code "36") (name "/LED_RED") (class "Default")
      (node (ref "LED1") (pin "1") (pinfunction "Red_1") (pintype "power_in"))
      (node (ref "R15") (pin "1") (pinfunction "1_1") (pintype "passive"))
      (node (ref "R15") (pin "2") (pinfunction "2_2") (pintype "passive"))
      (node (ref "U4") (pin "48") (pinfunction "PB11_48") (pintype "power_in"))
    )
    (net (code "37") (name "/MPU9250_SPI_CS") (class "Default")
      (node (ref "U4") (pin "17") (pinfunction "PC2_17") (pintype "power_in"))
      (node (ref "U6") (pin "22") (pinfunction "nCS_22") (pintype "power_in"))
    )
    (net (code "38") (name "/MPU9250_SPI_INT") (class "Default")
      (node (ref "U4") (pin "62") (pinfunction "PD15_62") (pintype "power_in"))
      (node (ref "U6") (pin "12") (pinfunction "INT_12") (pintype "power_in"))
    )
    (net (code "39") (name "/MPU9250_SPI_SCLK") (class "Default")
      (node (ref "U4") (pin "30") (pinfunction "PA5_30") (pintype "power_in"))
      (node (ref "U6") (pin "23") (pinfunction "SCL_/_SCLK_23") (pintype "power_in"))
    )
    (net (code "40") (name "/MPU9250_SPI_SDI") (class "Default")
      (node (ref "U4") (pin "32") (pinfunction "PA7_32") (pintype "power_in"))
      (node (ref "U6") (pin "24") (pinfunction "SDA_/_SDI_24") (pintype "power_in"))
    )
    (net (code "41") (name "/MPU9250_SPI_SDO") (class "Default")
      (node (ref "U4") (pin "31") (pinfunction "PA6_31") (pintype "power_in"))
      (node (ref "U6") (pin "9") (pinfunction "AD0_/_SDO_9") (pintype "power_in"))
    )
    (net (code "42") (name "/MS5607_SPI_ CS") (class "Default")
      (node (ref "U4") (pin "88") (pinfunction "PD7_88") (pintype "power_in"))
      (node (ref "U5") (pin "5") (pinfunction "CSB_5") (pintype "power_in"))
    )
    (net (code "43") (name "/MicroSD_CLK") (class "Default")
      (node (ref "U10") (pin "5") (pinfunction "CLK_5") (pintype "power_in"))
      (node (ref "U4") (pin "80") (pinfunction "PC12_80") (pintype "power_in"))
    )
    (net (code "44") (name "/MicroSD_CMD") (class "Default")
      (node (ref "R20") (pin "2") (pinfunction "2_2") (pintype "passive"))
      (node (ref "U10") (pin "3") (pinfunction "CMD_3") (pintype "power_in"))
      (node (ref "U4") (pin "83") (pinfunction "PD2_83") (pintype "power_in"))
    )
    (net (code "45") (name "/MicroSD_DAT0") (class "Default")
      (node (ref "R16") (pin "2") (pinfunction "2_2") (pintype "passive"))
      (node (ref "U10") (pin "7") (pinfunction "DAT0_7") (pintype "power_in"))
      (node (ref "U4") (pin "65") (pinfunction "PC8_65") (pintype "power_in"))
    )
    (net (code "46") (name "/MicroSD_DAT1") (class "Default")
      (node (ref "R17") (pin "2") (pinfunction "2_2") (pintype "passive"))
      (node (ref "U10") (pin "8") (pinfunction "DAT1_8") (pintype "power_in"))
      (node (ref "U4") (pin "66") (pinfunction "PC9_66") (pintype "power_in"))
    )
    (net (code "47") (name "/MicroSD_DAT2") (class "Default")
      (node (ref "R18") (pin "2") (pinfunction "2_2") (pintype "passive"))
      (node (ref "U10") (pin "1") (pinfunction "DAT2_1") (pintype "power_in"))
      (node (ref "U4") (pin "78") (pinfunction "PC10_78") (pintype "power_in"))
    )
    (net (code "48") (name "/MicroSD_DAT3") (class "Default")
      (node (ref "R19") (pin "2") (pinfunction "2_2") (pintype "passive"))
      (node (ref "U10") (pin "2") (pinfunction "CD/DAT3_2") (pintype "power_in"))
      (node (ref "U4") (pin "79") (pinfunction "PC11_79") (pintype "power_in"))
    )
    (net (code "49") (name "/NRST") (class "Default")
      (node (ref "U4") (pin "14") (pinfunction "NRST_14") (pintype "power_in"))
      (node (ref "U7") (pin "2") (pinfunction "Reset_2") (pintype "power_in"))
    )
    (net (code "50") (name "/OSC_IN") (class "Default")
      (node (ref "C15") (pin "2") (pinfunction "2_2") (pintype "passive"))
      (node (ref "U4") (pin "12") (pinfunction "PH0_12") (pintype "power_in"))
      (node (ref "X1") (pin "3") (pintype "power_in"))
    )
    (net (code "51") (name "/OSC_OUT") (class "Default")
      (node (ref "C25") (pin "1") (pinfunction "1_1") (pintype "passive"))
      (node (ref "U4") (pin "13") (pinfunction "PH1_13") (pintype "power_in"))
      (node (ref "X1") (pin "1") (pintype "power_in"))
    )
    (net (code "52") (name "/RC input") (class "Default")
      (node (ref "R14") (pin "2") (pinfunction "2_2") (pintype "passive"))
      (node (ref "U4") (pin "35") (pinfunction "PB0_35") (pintype "power_in"))
      (node (ref "U8") (pin "2") (pinfunction "1B_2") (pintype "power_in"))
    )
    (net (code "53") (name "/REGOUT") (class "Default")
      (node (ref "C26") (pin "2") (pinfunction "2_2") (pintype "passive"))
      (node (ref "U6") (pin "10") (pinfunction "REGOUT_10") (pintype "power_in"))
    )
    (net (code "54") (name "/RSSI_IN") (class "Default")
      (node (ref "U4") (pin "16") (pinfunction "PC1_16") (pintype "power_in"))
    )
    (net (code "55") (name "/SBUS_INV") (class "Default")
      (node (ref "U4") (pin "7") (pinfunction "PC13_7") (pintype "power_in"))
      (node (ref "U8") (pin "1") (pinfunction "1A_1") (pintype "power_in"))
    )
    (net (code "56") (name "/Sens. enable") (class "Default")
      (node (ref "U3") (pin "3") (pinfunction "EN_3") (pintype "power_in"))
      (node (ref "U4") (pin "2") (pinfunction "PE3_2") (pintype "power_in"))
    )
    (net (code "57") (name "/Telem1_UART_RX") (class "Default")
      (node (ref "U4") (pin "87") (pinfunction "PD6_87") (pintype "power_in"))
    )
    (net (code "58") (name "/Telem1_UART_TX") (class "Default")
      (node (ref "U4") (pin "86") (pinfunction "PD5_86") (pintype "power_in"))
    )
    (net (code "59") (name "/Telem2_UART_FMU_RX") (class "Default")
      (node (ref "U4") (pin "56") (pinfunction "PD9_56") (pintype "power_in"))
      (node (ref "U9") (pin "3") (pinfunction "A2_3") (pintype "power_in"))
    )
    (net (code "60") (name "/Telem2_UART_FMU_TX") (class "Default")
      (node (ref "U4") (pin "55") (pinfunction "PD8_55") (pintype "power_in"))
      (node (ref "U9") (pin "1") (pinfunction "A1_1") (pintype "power_in"))
    )
    (net (code "61") (name "/Telem2_UART_RX") (class "Default")
      (node (ref "U9") (pin "18") (pinfunction "B2_18") (pintype "power_in"))
    )
    (net (code "62") (name "/Telem2_UART_TX") (class "Default")
      (node (ref "U9") (pin "20") (pinfunction "B1_20") (pintype "power_in"))
    )
    (net (code "63") (name "/USB_D_N") (class "Default")
      (node (ref "U4") (pin "70") (pinfunction "PA11_70") (pintype "power_in"))
    )
    (net (code "64") (name "/USB_D_P") (class "Default")
      (node (ref "U4") (pin "71") (pinfunction "PA12_71") (pintype "power_in"))
    )
    (net (code "65") (name "/VBAT") (class "Default")
      (node (ref "C31") (pin "1") (pinfunction "1_1") (pintype "passive"))
      (node (ref "C32") (pin "1") (pinfunction "1_1") (pintype "passive"))
      (node (ref "D1") (pin "1") (pinfunction "1_1") (pintype "passive"))
      (node (ref "U4") (pin "6") (pinfunction "VBAT_6") (pintype "power_in"))
    )
    (net (code "66") (name "/VCAP_1") (class "Default")
      (node (ref "C33") (pin "1") (pinfunction "1_1") (pintype "passive"))
      (node (ref "U4") (pin "49") (pinfunction "VCAP_1_49") (pintype "power_in"))
    )
    (net (code "67") (name "/VCAP_2") (class "Default")
      (node (ref "C34") (pin "1") (pinfunction "1_1") (pintype "passive"))
      (node (ref "U4") (pin "73") (pinfunction "VCAP_2_73") (pintype "power_in"))
    )
    (net (code "68") (name "/Voltage sens.") (class "Default")
      (node (ref "U4") (pin "25") (pinfunction "PA2_25") (pintype "power_in"))
    )
    (net (code "69") (name "AGND") (class "Default")
      (node (ref "C14") (pin "2") (pinfunction "2_2") (pintype "passive"))
      (node (ref "L5") (pin "1") (pintype "power_in"))
      (node (ref "U4") (pin "20") (pinfunction "VSSA_20") (pintype "power_in"))
    )
    (net (code "70") (name "GND") (class "Default")
      (node (ref "C1") (pin "1") (pinfunction "1_1") (pintype "passive"))
      (node (ref "C10") (pin "1") (pinfunction "1_1") (pintype "passive"))
      (node (ref "C11") (pin "1") (pinfunction "1_1") (pintype "passive"))
      (node (ref "C12") (pin "1") (pinfunction "1_1") (pintype "passive"))
      (node (ref "C13") (pin "1") (pinfunction "1_1") (pintype "passive"))
      (node (ref "C15") (pin "1") (pinfunction "1_1") (pintype "passive"))
      (node (ref "C16") (pin "2") (pinfunction "2_2") (pintype "passive"))
      (node (ref "C17") (pin "2") (pinfunction "2_2") (pintype "passive"))
      (node (ref "C18") (pin "2") (pinfunction "2_2") (pintype "passive"))
      (node (ref "C19") (pin "2") (pinfunction "2_2") (pintype "passive"))
      (node (ref "C2") (pin "2") (pinfunction "2_2") (pintype "passive"))
      (node (ref "C20") (pin "2") (pinfunction "2_2") (pintype "passive"))
      (node (ref "C21") (pin "2") (pinfunction "2_2") (pintype "passive"))
      (node (ref "C22") (pin "1") (pinfunction "1_1") (pintype "passive"))
      (node (ref "C23") (pin "1") (pinfunction "1_1") (pintype "passive"))
      (node (ref "C24") (pin "1") (pinfunction "1_1") (pintype "passive"))
      (node (ref "C25") (pin "2") (pinfunction "2_2") (pintype "passive"))
      (node (ref "C26") (pin "1") (pinfunction "1_1") (pintype "passive"))
      (node (ref "C27") (pin "1") (pinfunction "1_1") (pintype "passive"))
      (node (ref "C28") (pin "1") (pinfunction "1_1") (pintype "passive"))
      (node (ref "C29") (pin "1") (pinfunction "1_1") (pintype "passive"))
      (node (ref "C3") (pin "2") (pinfunction "2_2") (pintype "passive"))
      (node (ref "C30") (pin "1") (pinfunction "1_1") (pintype "passive"))
      (node (ref "C31") (pin "2") (pinfunction "2_2") (pintype "passive"))
      (node (ref "C32") (pin "2") (pinfunction "2_2") (pintype "passive"))
      (node (ref "C33") (pin "2") (pinfunction "2_2") (pintype "passive"))
      (node (ref "C34") (pin "2") (pinfunction "2_2") (pintype "passive"))
      (node (ref "C35") (pin "1") (pinfunction "1_1") (pintype "passive"))
      (node (ref "C36") (pin "1") (pinfunction "1_1") (pintype "passive"))
      (node (ref "C37") (pin "2") (pinfunction "2_2") (pintype "passive"))
      (node (ref "C38") (pin "2") (pinfunction "2_2") (pintype "passive"))
      (node (ref "C4") (pin "2") (pinfunction "2_2") (pintype "passive"))
      (node (ref "C5") (pin "2") (pinfunction "2_2") (pintype "passive"))
      (node (ref "C56") (pin "1") (pinfunction "1_1") (pintype "passive"))
      (node (ref "C6") (pin "2") (pinfunction "2_2") (pintype "passive"))
      (node (ref "C7") (pin "2") (pinfunction "2_2") (pintype "passive"))
      (node (ref "C8") (pin "1") (pinfunction "1_1") (pintype "passive"))
      (node (ref "C9") (pin "1") (pinfunction "1_1") (pintype "passive"))
      (node (ref "L5") (pin "2") (pintype "power_in"))
      (node (ref "R1") (pin "2") (pinfunction "2_2") (pintype "passive"))
      (node (ref "R10") (pin "2") (pinfunction "2_2") (pintype "passive"))
      (node (ref "R14") (pin "1") (pinfunction "1_1") (pintype "passive"))
      (node (ref "R38") (pin "1") (pinfunction "1_1") (pintype "passive"))
      (node (ref "R5") (pin "2") (pinfunction "2_2") (pintype "passive"))
      (node (ref "R6") (pin "2") (pinfunction "2_2") (pintype "passive"))
      (node (ref "R7") (pin "1") (pinfunction "1_1") (pintype "passive"))
      (node (ref "R9") (pin "2") (pinfunction "2_2") (pintype "passive"))
      (node (ref "U1") (pin "2") (pinfunction "GND_2") (pintype "power_in"))
      (node (ref "U10") (pin "10") (pinfunction "GND_10") (pintype "power_in"))
      (node (ref "U10") (pin "6") (pinfunction "VSS_6") (pintype "power_in"))
      (node (ref "U10") (pin "9") (pinfunction "GND_9") (pintype "power_in"))
      (node (ref "U2") (pin "4") (pinfunction "VSS_4") (pintype "power_in"))
      (node (ref "U3") (pin "2") (pinfunction "GND_2") (pintype "power_in"))
      (node (ref "U4") (pin "10") (pinfunction "VSS_10") (pintype "power_in"))
      (node (ref "U4") (pin "27") (pinfunction "VSS_27") (pintype "power_in"))
      (node (ref "U4") (pin "74") (pinfunction "VSS_74") (pintype "power_in"))
      (node (ref "U4") (pin "99") (pinfunction "VSS_99") (pintype "power_in"))
      (node (ref "U5") (pin "2") (pinfunction "PS_2") (pintype "power_in"))
      (node (ref "U5") (pin "3") (pinfunction "GND_3") (pintype "power_in"))
      (node (ref "U6") (pin "11") (pinfunction "FSYNC_11") (pintype "power_in"))
      (node (ref "U6") (pin "18") (pinfunction "GND_18") (pintype "power_in"))
      (node (ref "U6") (pin "20") (pinfunction "RESV_20") (pintype "power_in"))
      (node (ref "U7") (pin "1") (pinfunction "GND_1") (pintype "power_in"))
      (node (ref "U8") (pin "4") (pinfunction "GND_4") (pintype "power_in"))
      (node (ref "U8") (pin "5") (pinfunction "2A_5") (pintype "power_in"))
      (node (ref "U8") (pin "6") (pinfunction "2B_6") (pintype "power_in"))
      (node (ref "U9") (pin "11") (pinfunction "GND_11") (pintype "power_in"))
      (node (ref "U9") (pin "21") (pinfunction "Exposed_pad_21") (pintype "power_in"))
      (node (ref "X1") (pin "2") (pinfunction "GND_2") (pintype "power_in"))
      (node (ref "X1") (pin "4") (pinfunction "GND_4") (pintype "power_in"))
    )
    (net (code "71") (name "unconnected-(U1-NC-Pad4)") (class "Default")
      (node (ref "U1") (pin "4") (pinfunction "NC_4") (pintype "open_collector"))
    )
    (net (code "72") (name "unconnected-(U3-NC-Pad4)") (class "Default")
      (node (ref "U3") (pin "4") (pinfunction "NC_4") (pintype "open_collector"))
    )
    (net (code "73") (name "unconnected-(U4-PA8-Pad67)") (class "Default")
      (node (ref "U4") (pin "67") (pinfunction "PA8_67") (pintype "power_in"))
    )
    (net (code "74") (name "unconnected-(U4-PA10-Pad69)") (class "Default")
      (node (ref "U4") (pin "69") (pinfunction "PA10_69") (pintype "power_in"))
    )
    (net (code "75") (name "unconnected-(U4-PA13-Pad72)") (class "Default")
      (node (ref "U4") (pin "72") (pinfunction "PA13_72") (pintype "power_in"))
    )
    (net (code "76") (name "unconnected-(U4-PA14-Pad76)") (class "Default")
      (node (ref "U4") (pin "76") (pinfunction "PA14_76") (pintype "power_in"))
    )
    (net (code "77") (name "unconnected-(U4-PA15-Pad77)") (class "Default")
      (node (ref "U4") (pin "77") (pinfunction "PA15_77") (pintype "power_in"))
    )
    (net (code "78") (name "unconnected-(U4-PB4-Pad90)") (class "Default")
      (node (ref "U4") (pin "90") (pinfunction "PB4_90") (pintype "power_in"))
    )
    (net (code "79") (name "unconnected-(U4-PB6-Pad92)") (class "Default")
      (node (ref "U4") (pin "92") (pinfunction "PB6_92") (pintype "power_in"))
    )
    (net (code "80") (name "unconnected-(U4-PB7-Pad93)") (class "Default")
      (node (ref "U4") (pin "93") (pinfunction "PB7_93") (pintype "power_in"))
    )
    (net (code "81") (name "unconnected-(U4-PB12-Pad51)") (class "Default")
      (node (ref "U4") (pin "51") (pinfunction "PB12_51") (pintype "power_in"))
    )
    (net (code "82") (name "unconnected-(U4-PB13-Pad52)") (class "Default")
      (node (ref "U4") (pin "52") (pinfunction "PB13_52") (pintype "power_in"))
    )
    (net (code "83") (name "unconnected-(U4-PC3-Pad18)") (class "Default")
      (node (ref "U4") (pin "18") (pinfunction "PC3_18") (pintype "power_in"))
    )
    (net (code "84") (name "unconnected-(U4-PC4-Pad33)") (class "Default")
      (node (ref "U4") (pin "33") (pinfunction "PC4_33") (pintype "power_in"))
    )
    (net (code "85") (name "unconnected-(U4-PC5-Pad34)") (class "Default")
      (node (ref "U4") (pin "34") (pinfunction "PC5_34") (pintype "power_in"))
    )
    (net (code "86") (name "unconnected-(U4-PC6-Pad63)") (class "Default")
      (node (ref "U4") (pin "63") (pinfunction "PC6_63") (pintype "power_in"))
    )
    (net (code "87") (name "unconnected-(U4-PC14-Pad8)") (class "Default")
      (node (ref "U4") (pin "8") (pinfunction "PC14_8") (pintype "power_in"))
    )
    (net (code "88") (name "unconnected-(U4-PC15-Pad9)") (class "Default")
      (node (ref "U4") (pin "9") (pinfunction "PC15_9") (pintype "power_in"))
    )
    (net (code "89") (name "unconnected-(U4-PD0-Pad81)") (class "Default")
      (node (ref "U4") (pin "81") (pinfunction "PD0_81") (pintype "power_in"))
    )
    (net (code "90") (name "unconnected-(U4-PD1-Pad82)") (class "Default")
      (node (ref "U4") (pin "82") (pinfunction "PD1_82") (pintype "power_in"))
    )
    (net (code "91") (name "unconnected-(U4-PD3-Pad84)") (class "Default")
      (node (ref "U4") (pin "84") (pinfunction "PD3_84") (pintype "power_in"))
    )
    (net (code "92") (name "unconnected-(U4-PD4-Pad85)") (class "Default")
      (node (ref "U4") (pin "85") (pinfunction "PD4_85") (pintype "power_in"))
    )
    (net (code "93") (name "unconnected-(U4-PD11-Pad58)") (class "Default")
      (node (ref "U4") (pin "58") (pinfunction "PD11_58") (pintype "power_in"))
    )
    (net (code "94") (name "unconnected-(U4-PD12-Pad59)") (class "Default")
      (node (ref "U4") (pin "59") (pinfunction "PD12_59") (pintype "power_in"))
    )
    (net (code "95") (name "unconnected-(U4-PE0-Pad97)") (class "Default")
      (node (ref "U4") (pin "97") (pinfunction "PE0_97") (pintype "power_in"))
    )
    (net (code "96") (name "unconnected-(U4-PE1-Pad98)") (class "Default")
      (node (ref "U4") (pin "98") (pinfunction "PE1_98") (pintype "power_in"))
    )
    (net (code "97") (name "unconnected-(U4-PE2-Pad1)") (class "Default")
      (node (ref "U4") (pin "1") (pinfunction "PE2_1") (pintype "power_in"))
    )
    (net (code "98") (name "unconnected-(U4-PE4-Pad3)") (class "Default")
      (node (ref "U4") (pin "3") (pinfunction "PE4_3") (pintype "power_in"))
    )
    (net (code "99") (name "unconnected-(U4-PE5-Pad4)") (class "Default")
      (node (ref "U4") (pin "4") (pinfunction "PE5_4") (pintype "power_in"))
    )
    (net (code "100") (name "unconnected-(U4-PE6-Pad5)") (class "Default")
      (node (ref "U4") (pin "5") (pinfunction "PE6_5") (pintype "power_in"))
    )
    (net (code "101") (name "unconnected-(U4-PE7-Pad38)") (class "Default")
      (node (ref "U4") (pin "38") (pinfunction "PE7_38") (pintype "power_in"))
    )
    (net (code "102") (name "unconnected-(U4-PE8-Pad39)") (class "Default")
      (node (ref "U4") (pin "39") (pinfunction "PE8_39") (pintype "power_in"))
    )
    (net (code "103") (name "unconnected-(U4-PE10-Pad41)") (class "Default")
      (node (ref "U4") (pin "41") (pinfunction "PE10_41") (pintype "power_in"))
    )
    (net (code "104") (name "unconnected-(U4-PE12-Pad43)") (class "Default")
      (node (ref "U4") (pin "43") (pinfunction "PE12_43") (pintype "power_in"))
    )
    (net (code "105") (name "unconnected-(U4-PE15-Pad46)") (class "Default")
      (node (ref "U4") (pin "46") (pinfunction "PE15_46") (pintype "power_in"))
    )
    (net (code "106") (name "unconnected-(U5-CSB-Pad4)") (class "Default")
      (node (ref "U5") (pin "4") (pinfunction "CSB_4") (pintype "power_in"))
    )
    (net (code "107") (name "unconnected-(U6-AUX_CL-Pad7)") (class "Default")
      (node (ref "U6") (pin "7") (pinfunction "AUX_CL_7") (pintype "power_in"))
    )
    (net (code "108") (name "unconnected-(U6-AUX_DA-Pad21)") (class "Default")
      (node (ref "U6") (pin "21") (pinfunction "AUX_DA_21") (pintype "power_in"))
    )
    (net (code "109") (name "unconnected-(U6-NC-Pad2)") (class "Default")
      (node (ref "U6") (pin "2") (pinfunction "NC_2") (pintype "power_in"))
    )
    (net (code "110") (name "unconnected-(U6-NC-Pad3)") (class "Default")
      (node (ref "U6") (pin "3") (pinfunction "NC_3") (pintype "power_in"))
    )
    (net (code "111") (name "unconnected-(U6-NC-Pad4)") (class "Default")
      (node (ref "U6") (pin "4") (pinfunction "NC_4") (pintype "power_in"))
    )
    (net (code "112") (name "unconnected-(U6-NC-Pad5)") (class "Default")
      (node (ref "U6") (pin "5") (pinfunction "NC_5") (pintype "power_in"))
    )
    (net (code "113") (name "unconnected-(U6-NC-Pad6)") (class "Default")
      (node (ref "U6") (pin "6") (pinfunction "NC_6") (pintype "power_in"))
    )
    (net (code "114") (name "unconnected-(U6-NC-Pad14)") (class "Default")
      (node (ref "U6") (pin "14") (pinfunction "NC_14") (pintype "power_in"))
    )
    (net (code "115") (name "unconnected-(U6-NC-Pad15)") (class "Default")
      (node (ref "U6") (pin "15") (pinfunction "NC_15") (pintype "power_in"))
    )
    (net (code "116") (name "unconnected-(U6-NC-Pad16)") (class "Default")
      (node (ref "U6") (pin "16") (pinfunction "NC_16") (pintype "power_in"))
    )
    (net (code "117") (name "unconnected-(U6-NC-Pad17)") (class "Default")
      (node (ref "U6") (pin "17") (pinfunction "NC_17") (pintype "power_in"))
    )
    (net (code "118") (name "unconnected-(U6-RESV-Pad19)") (class "Default")
      (node (ref "U6") (pin "19") (pinfunction "RESV_19") (pintype "power_in"))
    )
    (net (code "119") (name "unconnected-(U8-2Y-Pad3)") (class "Default")
      (node (ref "U8") (pin "3") (pinfunction "2Y_3") (pintype "power_in"))
    )
    (net (code "120") (name "unconnected-(U10-DET-Pad11)") (class "Default")
      (node (ref "U10") (pin "11") (pinfunction "DET_11") (pintype "power_in"))
    )
    (net (code "121") (name "unconnected-(U10-POL-Pad12)") (class "Default")
      (node (ref "U10") (pin "12") (pinfunction "POL_12") (pintype "power_in"))
    )
  )
)
